# PCBA-2075-02.net
KiCad netlist of a schematic drawn in Altium Designer
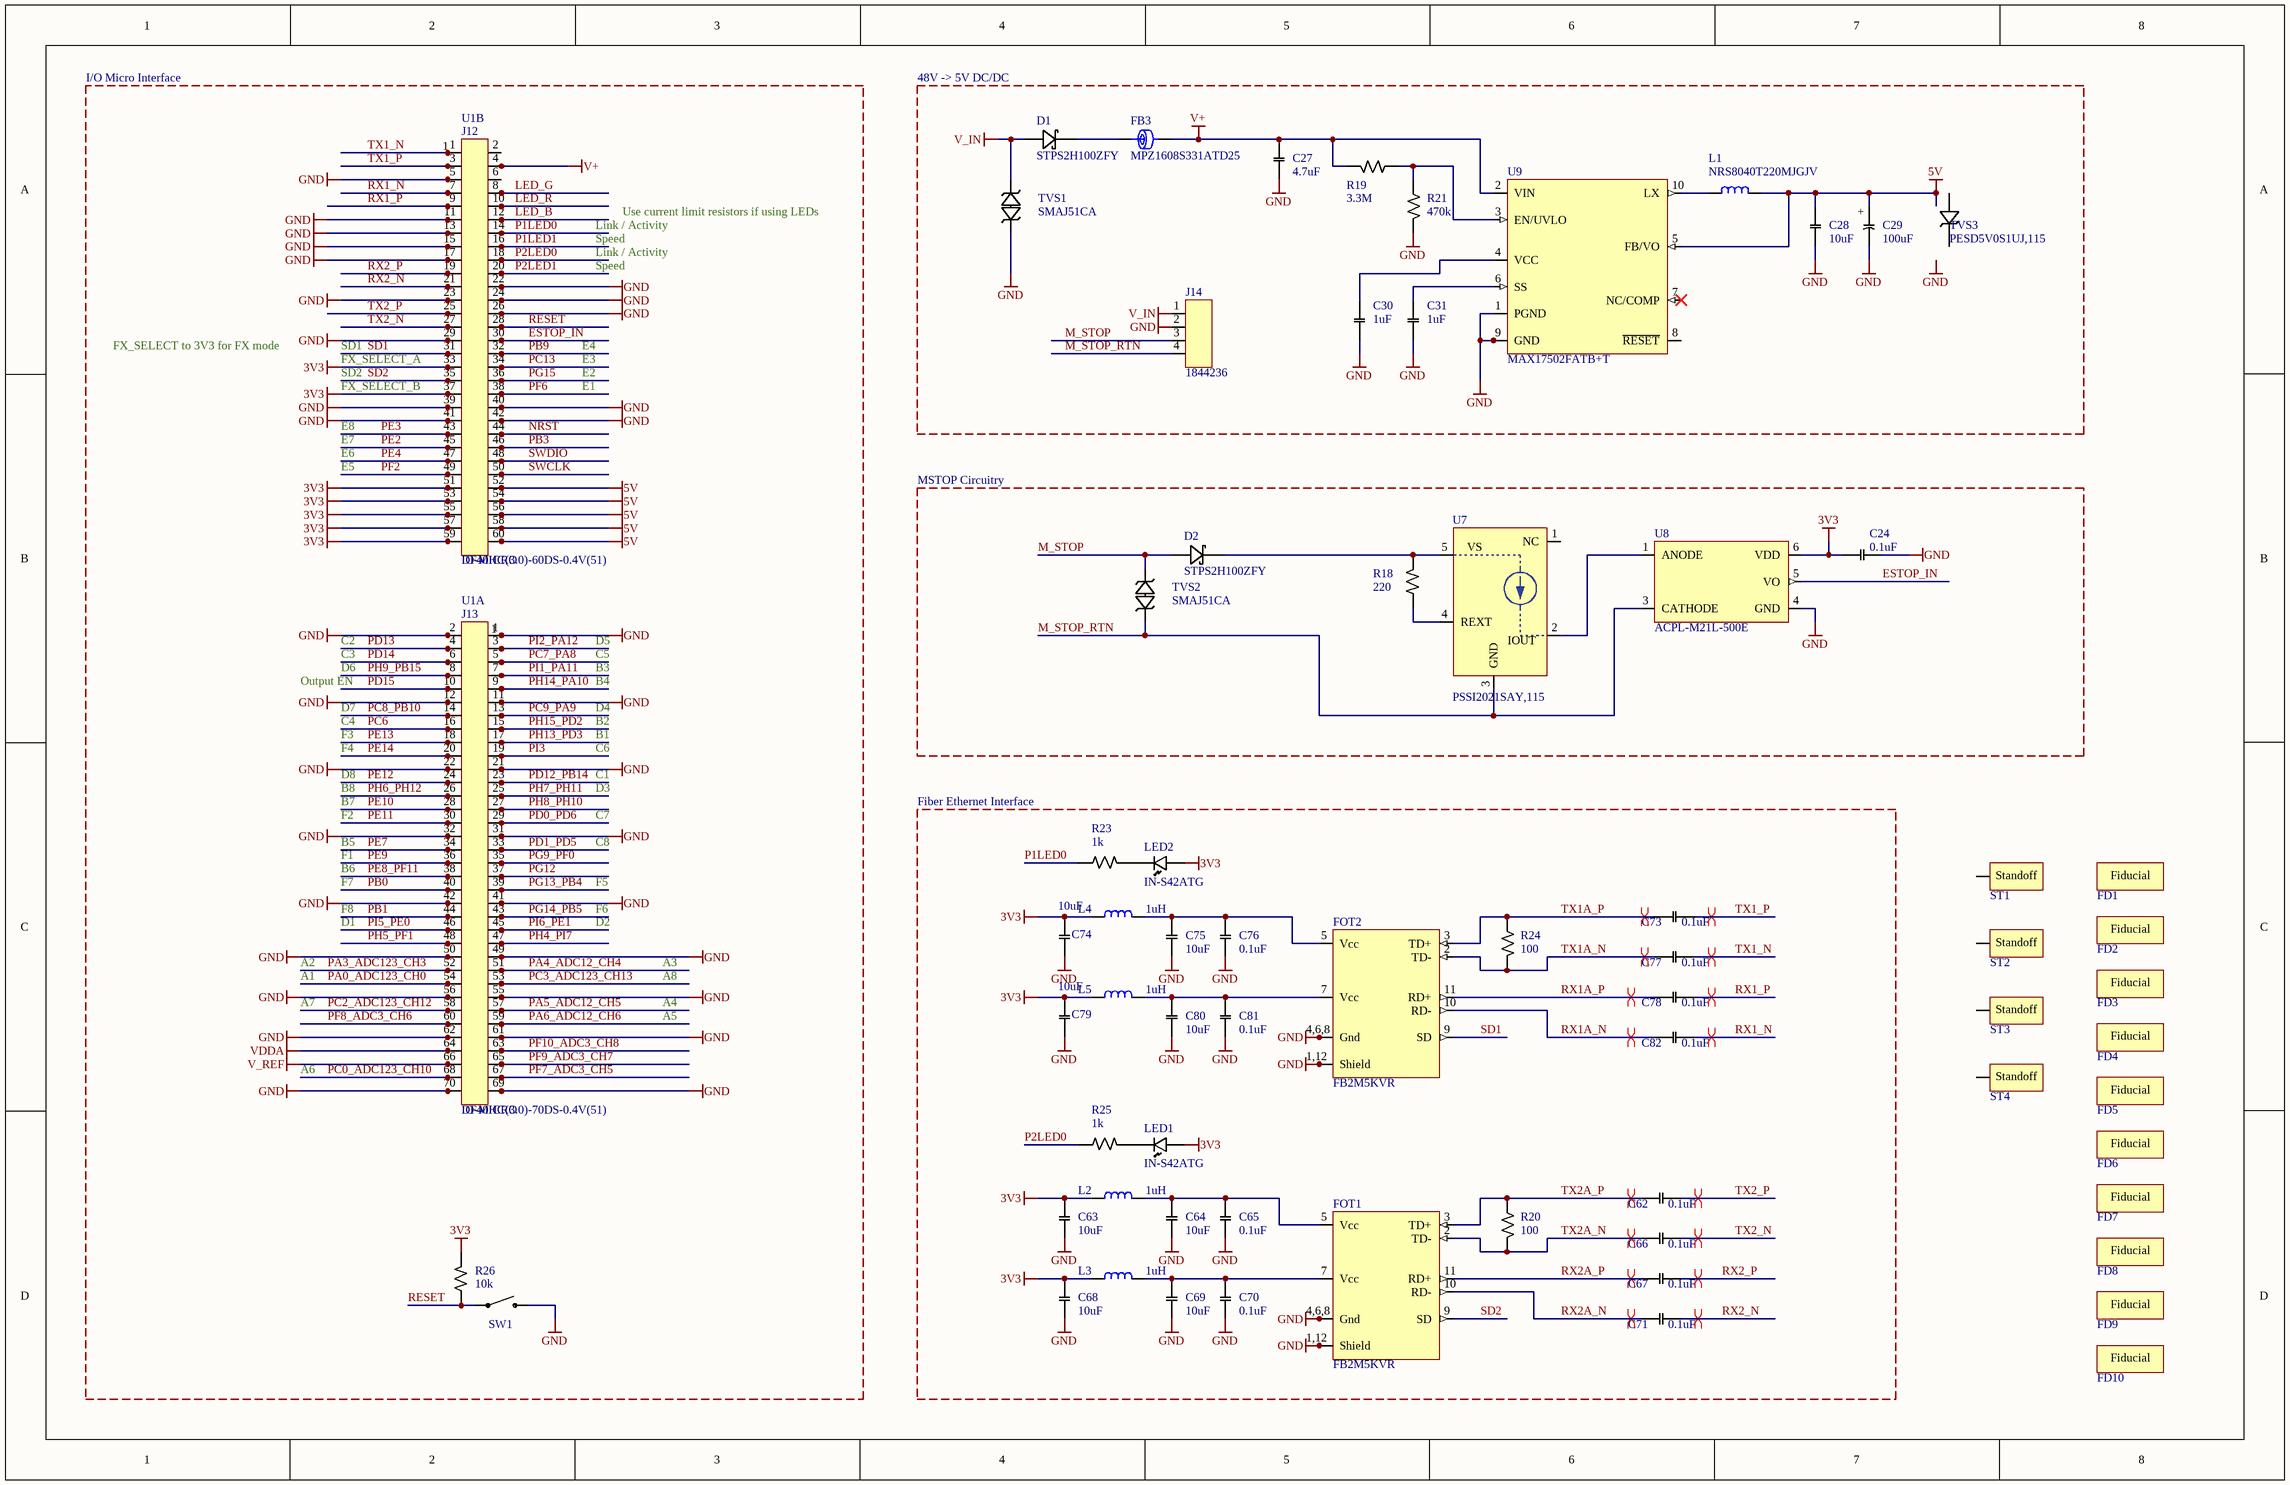
[diagram p0: PCBA-2075-02.SchDoc]

(export (version "E")
  (design (tool "Eeschema 10.0.6"))
  (components
    (comp (ref "C24")
      (value "CMP-00040-11")
      (footprint "C0402")
      (description "Capacitor Ceramic 0.1uF 25V X7R 10% SMD 0402")
      (fields (field (name "TOLERANCE") "10%") (field (name "CAPACITANCE") "0.1uF"))
      (libsource (lib "Hebi Robotics") (part "Capacitor"))
    )
    (comp (ref "C27")
      (value "C-4.7uf-X7S-100V-20%-1210")
      (footprint "C1210")
      (description "Capacitor Ceramic 4.7uF 100V X7S 20% SMD 1210")
      (fields (field (name "TOLERANCE") "±20%") (field (name "CAPACITANCE") "4.7uF"))
      (libsource (lib "Hebi Robotics") (part "Capacitor"))
    )
    (comp (ref "C28")
      (value "C-10uf-X5R-16V-10%-0603")
      (footprint "C0603")
      (description "Capacitor Ceramic 10uF 16V X5R 10% SMD 0603")
      (fields (field (name "TOLERANCE") "10%") (field (name "CAPACITANCE") "10uF"))
      (libsource (lib "Hebi Robotics") (part "Capacitor"))
    )
    (comp (ref "C29")
      (value "16SVPC100M")
      (footprint "CAPAE127P600-8N")
      (description "CAP ALUM POLY 100UF 20% 16V SMD")
      (fields
        (field (name "CAPACITANCE") "100uF")
        (field (name "TOLERANCE") "20%")
        (field (name "VOLTAGE") "16V")
      )
      (libsource (lib "Hebi Robotics") (part "Capacitor_Polarized"))
    )
    (comp (ref "C30")
      (value "C-1uf-X7R-25V-10%-0603")
      (footprint "C0603")
      (description "Capacitor Ceramic 1uF 25V X7R 10% SMD 0603")
      (fields (field (name "TOLERANCE") "10%") (field (name "CAPACITANCE") "1uF"))
      (libsource (lib "Hebi Robotics") (part "Capacitor"))
    )
    (comp (ref "C31")
      (value "C-1uf-X7R-25V-10%-0603")
      (footprint "C0603")
      (description "Capacitor Ceramic 1uF 25V X7R 10% SMD 0603")
      (fields (field (name "TOLERANCE") "10%") (field (name "CAPACITANCE") "1uF"))
      (libsource (lib "Hebi Robotics") (part "Capacitor"))
    )
    (comp (ref "C62")
      (value "CMP-00040-11")
      (footprint "C0402")
      (description "Capacitor Ceramic 0.1uF 25V X7R 10% SMD 0402")
      (fields (field (name "TOLERANCE") "10%") (field (name "CAPACITANCE") "0.1uF"))
      (libsource (lib "Hebi Robotics") (part "Capacitor"))
    )
    (comp (ref "C63")
      (value "C-10uf-X5R-16V-10%-0603")
      (footprint "C0603")
      (description "Capacitor Ceramic 10uF 16V X5R 10% SMD 0603")
      (fields (field (name "TOLERANCE") "10%") (field (name "CAPACITANCE") "10uF"))
      (libsource (lib "Hebi Robotics") (part "Capacitor"))
    )
    (comp (ref "C64")
      (value "C-10uf-X5R-16V-10%-0603")
      (footprint "C0603")
      (description "Capacitor Ceramic 10uF 16V X5R 10% SMD 0603")
      (fields (field (name "TOLERANCE") "10%") (field (name "CAPACITANCE") "10uF"))
      (libsource (lib "Hebi Robotics") (part "Capacitor"))
    )
    (comp (ref "C65")
      (value "CMP-00040-11")
      (footprint "C0402")
      (description "Capacitor Ceramic 0.1uF 25V X7R 10% SMD 0402")
      (fields (field (name "TOLERANCE") "10%") (field (name "CAPACITANCE") "0.1uF"))
      (libsource (lib "Hebi Robotics") (part "Capacitor"))
    )
    (comp (ref "C66")
      (value "CMP-00040-11")
      (footprint "C0402")
      (description "Capacitor Ceramic 0.1uF 25V X7R 10% SMD 0402")
      (fields (field (name "TOLERANCE") "10%") (field (name "CAPACITANCE") "0.1uF"))
      (libsource (lib "Hebi Robotics") (part "Capacitor"))
    )
    (comp (ref "C67")
      (value "CMP-00040-11")
      (footprint "C0402")
      (description "Capacitor Ceramic 0.1uF 25V X7R 10% SMD 0402")
      (fields (field (name "TOLERANCE") "10%") (field (name "CAPACITANCE") "0.1uF"))
      (libsource (lib "Hebi Robotics") (part "Capacitor"))
    )
    (comp (ref "C68")
      (value "C-10uf-X5R-16V-10%-0603")
      (footprint "C0603")
      (description "Capacitor Ceramic 10uF 16V X5R 10% SMD 0603")
      (fields (field (name "TOLERANCE") "10%") (field (name "CAPACITANCE") "10uF"))
      (libsource (lib "Hebi Robotics") (part "Capacitor"))
    )
    (comp (ref "C69")
      (value "C-10uf-X5R-16V-10%-0603")
      (footprint "C0603")
      (description "Capacitor Ceramic 10uF 16V X5R 10% SMD 0603")
      (fields (field (name "TOLERANCE") "10%") (field (name "CAPACITANCE") "10uF"))
      (libsource (lib "Hebi Robotics") (part "Capacitor"))
    )
    (comp (ref "C70")
      (value "CMP-00040-11")
      (footprint "C0402")
      (description "Capacitor Ceramic 0.1uF 25V X7R 10% SMD 0402")
      (fields (field (name "TOLERANCE") "10%") (field (name "CAPACITANCE") "0.1uF"))
      (libsource (lib "Hebi Robotics") (part "Capacitor"))
    )
    (comp (ref "C71")
      (value "CMP-00040-11")
      (footprint "C0402")
      (description "Capacitor Ceramic 0.1uF 25V X7R 10% SMD 0402")
      (fields (field (name "TOLERANCE") "10%") (field (name "CAPACITANCE") "0.1uF"))
      (libsource (lib "Hebi Robotics") (part "Capacitor"))
    )
    (comp (ref "C73")
      (value "CMP-00040-11")
      (footprint "C0402")
      (description "Capacitor Ceramic 0.1uF 25V X7R 10% SMD 0402")
      (fields (field (name "TOLERANCE") "10%") (field (name "CAPACITANCE") "0.1uF"))
      (libsource (lib "Hebi Robotics") (part "Capacitor"))
    )
    (comp (ref "C74")
      (value "C-10uf-X5R-16V-10%-0603")
      (footprint "C0603")
      (description "Capacitor Ceramic 10uF 16V X5R 10% SMD 0603")
      (fields (field (name "TOLERANCE") "10%") (field (name "CAPACITANCE") "10uF"))
      (libsource (lib "Hebi Robotics") (part "Capacitor"))
    )
    (comp (ref "C75")
      (value "C-10uf-X5R-16V-10%-0603")
      (footprint "C0603")
      (description "Capacitor Ceramic 10uF 16V X5R 10% SMD 0603")
      (fields (field (name "TOLERANCE") "10%") (field (name "CAPACITANCE") "10uF"))
      (libsource (lib "Hebi Robotics") (part "Capacitor"))
    )
    (comp (ref "C76")
      (value "CMP-00040-11")
      (footprint "C0402")
      (description "Capacitor Ceramic 0.1uF 25V X7R 10% SMD 0402")
      (fields (field (name "TOLERANCE") "10%") (field (name "CAPACITANCE") "0.1uF"))
      (libsource (lib "Hebi Robotics") (part "Capacitor"))
    )
    (comp (ref "C77")
      (value "CMP-00040-11")
      (footprint "C0402")
      (description "Capacitor Ceramic 0.1uF 25V X7R 10% SMD 0402")
      (fields (field (name "TOLERANCE") "10%") (field (name "CAPACITANCE") "0.1uF"))
      (libsource (lib "Hebi Robotics") (part "Capacitor"))
    )
    (comp (ref "C78")
      (value "CMP-00040-11")
      (footprint "C0402")
      (description "Capacitor Ceramic 0.1uF 25V X7R 10% SMD 0402")
      (fields (field (name "TOLERANCE") "10%") (field (name "CAPACITANCE") "0.1uF"))
      (libsource (lib "Hebi Robotics") (part "Capacitor"))
    )
    (comp (ref "C79")
      (value "C-10uf-X5R-16V-10%-0603")
      (footprint "C0603")
      (description "Capacitor Ceramic 10uF 16V X5R 10% SMD 0603")
      (fields (field (name "TOLERANCE") "10%") (field (name "CAPACITANCE") "10uF"))
      (libsource (lib "Hebi Robotics") (part "Capacitor"))
    )
    (comp (ref "C80")
      (value "C-10uf-X5R-16V-10%-0603")
      (footprint "C0603")
      (description "Capacitor Ceramic 10uF 16V X5R 10% SMD 0603")
      (fields (field (name "TOLERANCE") "10%") (field (name "CAPACITANCE") "10uF"))
      (libsource (lib "Hebi Robotics") (part "Capacitor"))
    )
    (comp (ref "C81")
      (value "CMP-00040-11")
      (footprint "C0402")
      (description "Capacitor Ceramic 0.1uF 25V X7R 10% SMD 0402")
      (fields (field (name "TOLERANCE") "10%") (field (name "CAPACITANCE") "0.1uF"))
      (libsource (lib "Hebi Robotics") (part "Capacitor"))
    )
    (comp (ref "C82")
      (value "CMP-00040-11")
      (footprint "C0402")
      (description "Capacitor Ceramic 0.1uF 25V X7R 10% SMD 0402")
      (fields (field (name "TOLERANCE") "10%") (field (name "CAPACITANCE") "0.1uF"))
      (libsource (lib "Hebi Robotics") (part "Capacitor"))
    )
    (comp (ref "D1")
      (value "STPS2H100ZFY")
      (footprint "SOD123F_ST")
      (description "DIODE SCHOTTKY 100V 2A SOD123F")
      (libsource (lib "Hebi Robotics") (part "SCHOTTKY"))
    )
    (comp (ref "D2")
      (value "STPS2H100ZFY")
      (footprint "SOD123F_ST")
      (description "DIODE SCHOTTKY 100V 2A SOD123F")
      (libsource (lib "Hebi Robotics") (part "SCHOTTKY"))
    )
    (comp (ref "FB3")
      (value "MPZ1608S331ATD25")
      (footprint "FB0603")
      (description "FERRITE CHIP 330 OHM 1.7A 0603")
      (libsource (lib "Hebi Robotics") (part "FB"))
    )
    (comp (ref "FD1")
      (value "FIDUCIAL")
      (footprint "fiducial_01")
      (description "Fiducial")
      (fields (field (name "MANUFACTURER PART NUMBER") "fiducial_01"))
      (libsource (lib "pcb_trace_components") (part "FIDUCIAL"))
    )
    (comp (ref "FD2")
      (value "FIDUCIAL")
      (footprint "fiducial_01")
      (description "Fiducial")
      (fields (field (name "MANUFACTURER PART NUMBER") "fiducial_01"))
      (libsource (lib "pcb_trace_components") (part "FIDUCIAL"))
    )
    (comp (ref "FD3")
      (value "FIDUCIAL")
      (footprint "fiducial_01")
      (description "Fiducial")
      (fields (field (name "MANUFACTURER PART NUMBER") "fiducial_01"))
      (libsource (lib "pcb_trace_components") (part "FIDUCIAL"))
    )
    (comp (ref "FD4")
      (value "FIDUCIAL")
      (footprint "fiducial_01")
      (description "Fiducial")
      (fields (field (name "MANUFACTURER PART NUMBER") "fiducial_01"))
      (libsource (lib "pcb_trace_components") (part "FIDUCIAL"))
    )
    (comp (ref "FD5")
      (value "*")
      (footprint "fiducial_01_no_overlay")
      (description "Fiducial with no overlay")
      (fields (field (name "MANUFACTURER PART NUMBER") "fiducial_01_no_overlay"))
      (libsource (lib "pcb_trace_components") (part "FIDUCIAL"))
    )
    (comp (ref "FD6")
      (value "*")
      (footprint "fiducial_01_no_overlay")
      (description "Fiducial with no overlay")
      (fields (field (name "MANUFACTURER PART NUMBER") "fiducial_01_no_overlay"))
      (libsource (lib "pcb_trace_components") (part "FIDUCIAL"))
    )
    (comp (ref "FD7")
      (value "*")
      (footprint "fiducial_01_no_overlay")
      (description "Fiducial with no overlay")
      (fields (field (name "MANUFACTURER PART NUMBER") "fiducial_01_no_overlay"))
      (libsource (lib "pcb_trace_components") (part "FIDUCIAL"))
    )
    (comp (ref "FD8")
      (value "*")
      (footprint "fiducial_01_no_overlay")
      (description "Fiducial with no overlay")
      (fields (field (name "MANUFACTURER PART NUMBER") "fiducial_01_no_overlay"))
      (libsource (lib "pcb_trace_components") (part "FIDUCIAL"))
    )
    (comp (ref "FD9")
      (value "*")
      (footprint "fiducial_01_no_overlay")
      (description "Fiducial with no overlay")
      (fields (field (name "MANUFACTURER PART NUMBER") "fiducial_01_no_overlay"))
      (libsource (lib "pcb_trace_components") (part "FIDUCIAL"))
    )
    (comp (ref "FD10")
      (value "*")
      (footprint "fiducial_01_no_overlay")
      (description "Fiducial with no overlay")
      (fields (field (name "MANUFACTURER PART NUMBER") "fiducial_01_no_overlay"))
      (libsource (lib "pcb_trace_components") (part "FIDUCIAL"))
    )
    (comp (ref "FOT1")
      (value "FB2M5KVR")
      (footprint "OPTOLOCK")
      (description "Industrial Ethernet Fiber Optic")
      (fields (field (name "MANUFACTURER") "Firecomms"))
      (libsource (lib "Hebi Robotics") (part "OPTOLOCK_D"))
    )
    (comp (ref "FOT2")
      (value "FB2M5KVR")
      (footprint "OPTOLOCK")
      (description "Industrial Ethernet Fiber Optic")
      (fields (field (name "MANUFACTURER") "Firecomms"))
      (libsource (lib "Hebi Robotics") (part "OPTOLOCK_D"))
    )
    (comp (ref "J12")
      (value "DF40HC(3.0)-60DS-0.4V(51)")
      (footprint "DF40HC(3.0)-60DS-0.4V(51)")
      (description "CONN RCPT 60POS 0.4MM SMD GOLD")
      (libsource (lib "Hebi Robotics") (part "CONN_2_ROW_060_POS"))
    )
    (comp (ref "J13")
      (value "DF40HC(3.0)-70DS-0.4V(51)")
      (footprint "DF40HC(3.0)-70DS-0.4V(51)")
      (description "CONN RCPT 70POS 0.4MM SMD GOLD")
      (fields (field (name "MANUFACTURER") "Hirose"))
      (libsource (lib "Hebi Robotics") (part "CONN_2_ROW_070_POS"))
    )
    (comp (ref "J14")
      (value "1844236")
      (footprint "1844236")
      (description "HEADER TERM BLOCK 3.5MM 4POS")
      (fields (field (name "MANUFACTURER") "Phoenix Contact"))
      (libsource (lib "Hebi Robotics") (part "CONN_1_ROW_004_POS"))
    )
    (comp (ref "L1")
      (value "NRS8040T220MJGJV")
      (footprint "NR8040T220M")
      (description "FIXED IND 22UH 2.2A 85.8 MOHM")
      (fields (field (name "TOLERANCE") "±20%"))
      (libsource (lib "Hebi Robotics") (part "Inductor"))
    )
    (comp (ref "L2")
      (value "ASMPH-0603-1R0M-T")
      (footprint "I0603")
      (description "FIXED IND 1UH 1A 200 MOHM SMD")
      (fields (field (name "TOLERANCE") "20%") (field (name "INDUCTANCE") "1uH"))
      (libsource (lib "Hebi Robotics") (part "Inductor"))
    )
    (comp (ref "L3")
      (value "ASMPH-0603-1R0M-T")
      (footprint "I0603")
      (description "FIXED IND 1UH 1A 200 MOHM SMD")
      (fields (field (name "TOLERANCE") "20%") (field (name "INDUCTANCE") "1uH"))
      (libsource (lib "Hebi Robotics") (part "Inductor"))
    )
    (comp (ref "L4")
      (value "ASMPH-0603-1R0M-T")
      (footprint "I0603")
      (description "FIXED IND 1UH 1A 200 MOHM SMD")
      (fields (field (name "TOLERANCE") "20%") (field (name "INDUCTANCE") "1uH"))
      (libsource (lib "Hebi Robotics") (part "Inductor"))
    )
    (comp (ref "L5")
      (value "ASMPH-0603-1R0M-T")
      (footprint "I0603")
      (description "FIXED IND 1UH 1A 200 MOHM SMD")
      (fields (field (name "TOLERANCE") "20%") (field (name "INDUCTANCE") "1uH"))
      (libsource (lib "Hebi Robotics") (part "Inductor"))
    )
    (comp (ref "LED1")
      (value "IN-S42ATG")
      (footprint "IN-S42AT")
      (description "LED GREEN CLEAR 0402 SMD")
      (libsource (lib "Hebi Robotics") (part "LED"))
    )
    (comp (ref "LED2")
      (value "IN-S42ATG")
      (footprint "IN-S42AT")
      (description "LED GREEN CLEAR 0402 SMD")
      (libsource (lib "Hebi Robotics") (part "LED"))
    )
    (comp (ref "R18")
      (value "R-220-1%-0.25w-0603")
      (footprint "R0603")
      (description "Resistor 0603 220 Ohm 1% 1-4 Watt")
      (fields (field (name "POWER") "0.25W, 1/4W") (field (name "RESISTANCE") "220"))
      (libsource (lib "Hebi Robotics") (part "Resistor"))
    )
    (comp (ref "R19")
      (value "R-3.3M-1%-0.063w-0402")
      (footprint "R0402")
      (description "Resistor 0402 3.3M Ohm 1% 1-16 Watt")
      (fields (field (name "POWER") "0.063W, 1/16W") (field (name "RESISTANCE") "3.3M"))
      (libsource (lib "Hebi Robotics") (part "Resistor"))
    )
    (comp (ref "R20")
      (value "100")
      (footprint "R0402")
      (description "Resistor 0402 100 Ohm 1% 1-16 Watt")
      (fields (field (name "POWER") "0.063W, 1/16W") (field (name "TOLERANCE") "1%"))
      (libsource (lib "Hebi Robotics") (part "Resistor"))
    )
    (comp (ref "R21")
      (value "R-470k-1%-0.063w-0402")
      (footprint "R0402")
      (description "Resistor 0402 470k Ohm 1% 1-16 Watt")
      (fields
        (field (name "POWER") "0.063W, 1/16W")
        (field (name "RESISTANCE") "470k")
        (field (name "TOLERANCE") "1%")
      )
      (libsource (lib "Hebi Robotics") (part "Resistor"))
    )
    (comp (ref "R23")
      (value "R-1k-1%-0.063w-0402")
      (footprint "R0402")
      (description "Resistor 0402 1k Ohm 1% 1-16 Watt")
      (fields
        (field (name "POWER") "0.063W, 1/16W")
        (field (name "RESISTANCE") "1k")
        (field (name "TOLERANCE") "1%")
      )
      (libsource (lib "Hebi Robotics") (part "Resistor"))
    )
    (comp (ref "R24")
      (value "100")
      (footprint "R0402")
      (description "Resistor 0402 100 Ohm 1% 1-16 Watt")
      (fields (field (name "POWER") "0.063W, 1/16W") (field (name "TOLERANCE") "1%"))
      (libsource (lib "Hebi Robotics") (part "Resistor"))
    )
    (comp (ref "R25")
      (value "R-1k-1%-0.063w-0402")
      (footprint "R0402")
      (description "Resistor 0402 1k Ohm 1% 1-16 Watt")
      (fields
        (field (name "POWER") "0.063W, 1/16W")
        (field (name "RESISTANCE") "1k")
        (field (name "TOLERANCE") "1%")
      )
      (libsource (lib "Hebi Robotics") (part "Resistor"))
    )
    (comp (ref "R26")
      (value "R-10k-1%-0.063w-0402")
      (footprint "R0402")
      (description "Resistor 0402 10k Ohm 1% 1-16 Watt")
      (fields
        (field (name "POWER") "0.063W, 1/16W")
        (field (name "RESISTANCE") "10k")
        (field (name "TOLERANCE") "1%")
      )
      (libsource (lib "Hebi Robotics") (part "Resistor"))
    )
    (comp (ref "ST1")
      (value "9774030960R")
      (footprint "9774030960R")
      (description "ROUND SPACER M3.3 STEEL 3MM")
      (fields (field (name "MANUFACTURER") "Wurth Electronics Inc"))
      (libsource (lib "Hebi Robotics") (part "STANDOFF_PIN"))
    )
    (comp (ref "ST2")
      (value "9774030960R")
      (footprint "9774030960R")
      (description "ROUND SPACER M3.3 STEEL 3MM")
      (fields (field (name "MANUFACTURER") "Wurth Electronics Inc"))
      (libsource (lib "Hebi Robotics") (part "STANDOFF_PIN"))
    )
    (comp (ref "ST3")
      (value "9774030960R")
      (footprint "9774030960R")
      (description "ROUND SPACER M3.3 STEEL 3MM")
      (fields (field (name "MANUFACTURER") "Wurth Electronics Inc"))
      (libsource (lib "Hebi Robotics") (part "STANDOFF_PIN"))
    )
    (comp (ref "ST4")
      (value "9774030960R")
      (footprint "9774030960R")
      (description "ROUND SPACER M3.3 STEEL 3MM")
      (fields (field (name "MANUFACTURER") "Wurth Electronics Inc"))
      (libsource (lib "Hebi Robotics") (part "STANDOFF_PIN"))
    )
    (comp (ref "SW1")
      (value "222ADVBA")
      (footprint "222ADVBA")
      (description "Tactile Switch SPST-NO Top Actuated Through Hole")
      (fields (field (name "MANUFACTURER") "CTS"))
      (libsource (lib "Hebi Robotics") (part "SPST_NO"))
    )
    (comp (ref "TVS1")
      (value "SMAJ51CA")
      (footprint "SMA_BI_BOURNS")
      (description "TVS DIODE 51VWM 82.4VC DO214AC")
      (libsource (lib "Hebi Robotics") (part "TVS_BI"))
    )
    (comp (ref "TVS2")
      (value "SMAJ51CA")
      (footprint "SMA_BI_BOURNS")
      (description "TVS DIODE 51VWM 82.4VC DO214AC")
      (libsource (lib "Hebi Robotics") (part "TVS_BI"))
    )
    (comp (ref "TVS3")
      (value "PESD5V0S1UJ,115")
      (footprint "SOD-323F_NXP")
      (description "TVS DIODE 5VWM 19VC SOD323F")
      (libsource (lib "Hebi Robotics") (part "TVS"))
    )
    (comp (ref "U1")
      (value "IO-MICRO")
      (footprint "IO-MICRO-Footprint-1")
      (description "IO Micro Composite Component")
      (libsource (lib "Hebi Robotics") (part "IO-MICRO-Symbol-1"))
    )
    (comp (ref "U7")
      (value "PSSI2021SAY,115")
      (footprint "PSSI2021SAY,115")
      (description "Current Source Regulator  50mA 5-TSSOP")
      (libsource (lib "Hebi Robotics") (part "PSSI2021SAY,115"))
    )
    (comp (ref "U8")
      (value "ACPL-M21L-500E")
      (footprint "SOT125P700X260-5N")
      (description "OPTOISO 3.75KV PUSH PULL 5SO")
      (libsource (lib "Hebi Robotics") (part "Symbol"))
    )
    (comp (ref "U9")
      (value "MAX17502FATB+T")
      (footprint "10_TDFN_MAXIM")
      (description "IC REG BUCK 5V 1A SYNC 10TDFN")
      (fields (field (name "MANUFACTURER") "Maxim Integrated"))
      (libsource (lib "Hebi Robotics") (part "MAX17502E_F_G"))
    )
  )
  (nets
    (net (code "1") (name "/ESTOP_IN") (class "Default")
      (node (ref "J12") (pin "30") (pinfunction "30_30") (pintype "passive"))
      (node (ref "U1") (pin "B30") (pinfunction "B30_B30") (pintype "passive"))
      (node (ref "U8") (pin "5") (pinfunction "VO_5") (pintype "output"))
    )
    (net (code "2") (name "/LED_B") (class "Default")
      (node (ref "J12") (pin "12") (pinfunction "12_12") (pintype "passive"))
      (node (ref "U1") (pin "B12") (pinfunction "B12_B12") (pintype "passive"))
    )
    (net (code "3") (name "/LED_G") (class "Default")
      (node (ref "J12") (pin "8") (pinfunction "8_8") (pintype "passive"))
      (node (ref "U1") (pin "B8") (pinfunction "B8_B8") (pintype "passive"))
    )
    (net (code "4") (name "/LED_R") (class "Default")
      (node (ref "J12") (pin "10") (pinfunction "10_10") (pintype "passive"))
      (node (ref "U1") (pin "B10") (pinfunction "B10_B10") (pintype "passive"))
    )
    (net (code "5") (name "/M_STOP") (class "Default")
      (node (ref "D2") (pin "A") (pinfunction "A_A") (pintype "passive"))
      (node (ref "J14") (pin "3") (pinfunction "3_3") (pintype "passive"))
      (node (ref "TVS2") (pin "C") (pinfunction "C_C") (pintype "passive"))
    )
    (net (code "6") (name "/M_STOP_RTN") (class "Default")
      (node (ref "J14") (pin "4") (pinfunction "4_4") (pintype "passive"))
      (node (ref "TVS2") (pin "A") (pinfunction "A_A") (pintype "passive"))
      (node (ref "U7") (pin "3") (pinfunction "GND_3") (pintype "passive"))
      (node (ref "U8") (pin "3") (pinfunction "CATHODE_3") (pintype "passive"))
    )
    (net (code "7") (name "/NRST") (class "Default")
      (node (ref "J12") (pin "44") (pinfunction "44_44") (pintype "passive"))
      (node (ref "U1") (pin "B44") (pinfunction "B44_B44") (pintype "passive"))
    )
    (net (code "8") (name "/P1LED0") (class "Default")
      (node (ref "J12") (pin "14") (pinfunction "14_14") (pintype "passive"))
      (node (ref "R23") (pin "1") (pinfunction "1_1") (pintype "passive"))
      (node (ref "U1") (pin "B14") (pinfunction "B14_B14") (pintype "passive"))
    )
    (net (code "9") (name "/P1LED1") (class "Default")
      (node (ref "J12") (pin "16") (pinfunction "16_16") (pintype "passive"))
      (node (ref "U1") (pin "B16") (pinfunction "B16_B16") (pintype "passive"))
    )
    (net (code "10") (name "/P2LED0") (class "Default")
      (node (ref "J12") (pin "18") (pinfunction "18_18") (pintype "passive"))
      (node (ref "R25") (pin "1") (pinfunction "1_1") (pintype "passive"))
      (node (ref "U1") (pin "B18") (pinfunction "B18_B18") (pintype "passive"))
    )
    (net (code "11") (name "/P2LED1") (class "Default")
      (node (ref "J12") (pin "20") (pinfunction "20_20") (pintype "passive"))
      (node (ref "U1") (pin "B20") (pinfunction "B20_B20") (pintype "passive"))
    )
    (net (code "12") (name "/PA0_ADC123_CH0") (class "Default")
      (node (ref "J13") (pin "54") (pinfunction "54_54") (pintype "passive"))
      (node (ref "U1") (pin "A54") (pinfunction "A54_A54") (pintype "passive"))
    )
    (net (code "13") (name "/PA3_ADC123_CH3") (class "Default")
      (node (ref "J13") (pin "52") (pinfunction "52_52") (pintype "passive"))
      (node (ref "U1") (pin "A52") (pinfunction "A52_A52") (pintype "passive"))
    )
    (net (code "14") (name "/PA4_ADC12_CH4") (class "Default")
      (node (ref "J13") (pin "51") (pinfunction "51_51") (pintype "passive"))
      (node (ref "U1") (pin "A51") (pinfunction "A51_A51") (pintype "passive"))
    )
    (net (code "15") (name "/PA5_ADC12_CH5") (class "Default")
      (node (ref "J13") (pin "57") (pinfunction "57_57") (pintype "passive"))
      (node (ref "U1") (pin "A57") (pinfunction "A57_A57") (pintype "passive"))
    )
    (net (code "16") (name "/PA6_ADC12_CH6") (class "Default")
      (node (ref "J13") (pin "59") (pinfunction "59_59") (pintype "passive"))
      (node (ref "U1") (pin "A59") (pinfunction "A59_A59") (pintype "passive"))
    )
    (net (code "17") (name "/PB0") (class "Default")
      (node (ref "J13") (pin "40") (pinfunction "40_40") (pintype "passive"))
      (node (ref "U1") (pin "A40") (pinfunction "A40_A40") (pintype "passive"))
    )
    (net (code "18") (name "/PB1") (class "Default")
      (node (ref "J13") (pin "44") (pinfunction "44_44") (pintype "passive"))
      (node (ref "U1") (pin "A44") (pinfunction "A44_A44") (pintype "passive"))
    )
    (net (code "19") (name "/PB3") (class "Default")
      (node (ref "J12") (pin "46") (pinfunction "46_46") (pintype "passive"))
      (node (ref "U1") (pin "B46") (pinfunction "B46_B46") (pintype "passive"))
    )
    (net (code "20") (name "/PB9") (class "Default")
      (node (ref "J12") (pin "32") (pinfunction "32_32") (pintype "passive"))
      (node (ref "U1") (pin "B32") (pinfunction "B32_B32") (pintype "passive"))
    )
    (net (code "21") (name "/PC0_ADC123_CH10") (class "Default")
      (node (ref "J13") (pin "68") (pinfunction "68_68") (pintype "passive"))
      (node (ref "U1") (pin "A68") (pinfunction "A68_A68") (pintype "passive"))
    )
    (net (code "22") (name "/PC2_ADC123_CH12") (class "Default")
      (node (ref "J13") (pin "58") (pinfunction "58_58") (pintype "passive"))
      (node (ref "U1") (pin "A58") (pinfunction "A58_A58") (pintype "passive"))
    )
    (net (code "23") (name "/PC3_ADC123_CH13") (class "Default")
      (node (ref "J13") (pin "53") (pinfunction "53_53") (pintype "passive"))
      (node (ref "U1") (pin "A53") (pinfunction "A53_A53") (pintype "passive"))
    )
    (net (code "24") (name "/PC6") (class "Default")
      (node (ref "J13") (pin "16") (pinfunction "16_16") (pintype "passive"))
      (node (ref "U1") (pin "A16") (pinfunction "A16_A16") (pintype "passive"))
    )
    (net (code "25") (name "/PC7_PA8") (class "Default")
      (node (ref "J13") (pin "5") (pinfunction "5_5") (pintype "passive"))
      (node (ref "U1") (pin "A5") (pinfunction "A5_A5") (pintype "passive"))
    )
    (net (code "26") (name "/PC8_PB10") (class "Default")
      (node (ref "J13") (pin "14") (pinfunction "14_14") (pintype "passive"))
      (node (ref "U1") (pin "A14") (pinfunction "A14_A14") (pintype "passive"))
    )
    (net (code "27") (name "/PC9_PA9") (class "Default")
      (node (ref "J13") (pin "13") (pinfunction "13_13") (pintype "passive"))
      (node (ref "U1") (pin "A13") (pinfunction "A13_A13") (pintype "passive"))
    )
    (net (code "28") (name "/PC13") (class "Default")
      (node (ref "J12") (pin "34") (pinfunction "34_34") (pintype "passive"))
      (node (ref "U1") (pin "B34") (pinfunction "B34_B34") (pintype "passive"))
    )
    (net (code "29") (name "/PD0_PD6") (class "Default")
      (node (ref "J13") (pin "29") (pinfunction "29_29") (pintype "passive"))
      (node (ref "U1") (pin "A29") (pinfunction "A29_A29") (pintype "passive"))
    )
    (net (code "30") (name "/PD1_PD5") (class "Default")
      (node (ref "J13") (pin "33") (pinfunction "33_33") (pintype "passive"))
      (node (ref "U1") (pin "A33") (pinfunction "A33_A33") (pintype "passive"))
    )
    (net (code "31") (name "/PD12_PB14") (class "Default")
      (node (ref "J13") (pin "23") (pinfunction "23_23") (pintype "passive"))
      (node (ref "U1") (pin "A23") (pinfunction "A23_A23") (pintype "passive"))
    )
    (net (code "32") (name "/PD13") (class "Default")
      (node (ref "J13") (pin "4") (pinfunction "4_4") (pintype "passive"))
      (node (ref "U1") (pin "A4") (pinfunction "A4_A4") (pintype "passive"))
    )
    (net (code "33") (name "/PD14") (class "Default")
      (node (ref "J13") (pin "6") (pinfunction "6_6") (pintype "passive"))
      (node (ref "U1") (pin "A6") (pinfunction "A6_A6") (pintype "passive"))
    )
    (net (code "34") (name "/PD15") (class "Default")
      (node (ref "J13") (pin "10") (pinfunction "10_10") (pintype "passive"))
      (node (ref "U1") (pin "A10") (pinfunction "A10_A10") (pintype "passive"))
    )
    (net (code "35") (name "/PE2") (class "Default")
      (node (ref "J12") (pin "45") (pinfunction "45_45") (pintype "passive"))
      (node (ref "U1") (pin "B45") (pinfunction "B45_B45") (pintype "passive"))
    )
    (net (code "36") (name "/PE3") (class "Default")
      (node (ref "J12") (pin "43") (pinfunction "43_43") (pintype "passive"))
      (node (ref "U1") (pin "B43") (pinfunction "B43_B43") (pintype "passive"))
    )
    (net (code "37") (name "/PE4") (class "Default")
      (node (ref "J12") (pin "47") (pinfunction "47_47") (pintype "passive"))
      (node (ref "U1") (pin "B47") (pinfunction "B47_B47") (pintype "passive"))
    )
    (net (code "38") (name "/PE7") (class "Default")
      (node (ref "J13") (pin "34") (pinfunction "34_34") (pintype "passive"))
      (node (ref "U1") (pin "A34") (pinfunction "A34_A34") (pintype "passive"))
    )
    (net (code "39") (name "/PE8_PF11") (class "Default")
      (node (ref "J13") (pin "38") (pinfunction "38_38") (pintype "passive"))
      (node (ref "U1") (pin "A38") (pinfunction "A38_A38") (pintype "passive"))
    )
    (net (code "40") (name "/PE9") (class "Default")
      (node (ref "J13") (pin "36") (pinfunction "36_36") (pintype "passive"))
      (node (ref "U1") (pin "A36") (pinfunction "A36_A36") (pintype "passive"))
    )
    (net (code "41") (name "/PE10") (class "Default")
      (node (ref "J13") (pin "28") (pinfunction "28_28") (pintype "passive"))
      (node (ref "U1") (pin "A28") (pinfunction "A28_A28") (pintype "passive"))
    )
    (net (code "42") (name "/PE11") (class "Default")
      (node (ref "J13") (pin "30") (pinfunction "30_30") (pintype "passive"))
      (node (ref "U1") (pin "A30") (pinfunction "A30_A30") (pintype "passive"))
    )
    (net (code "43") (name "/PE12") (class "Default")
      (node (ref "J13") (pin "24") (pinfunction "24_24") (pintype "passive"))
      (node (ref "U1") (pin "A24") (pinfunction "A24_A24") (pintype "passive"))
    )
    (net (code "44") (name "/PE13") (class "Default")
      (node (ref "J13") (pin "18") (pinfunction "18_18") (pintype "passive"))
      (node (ref "U1") (pin "A18") (pinfunction "A18_A18") (pintype "passive"))
    )
    (net (code "45") (name "/PE14") (class "Default")
      (node (ref "J13") (pin "20") (pinfunction "20_20") (pintype "passive"))
      (node (ref "U1") (pin "A20") (pinfunction "A20_A20") (pintype "passive"))
    )
    (net (code "46") (name "/PF2") (class "Default")
      (node (ref "J12") (pin "49") (pinfunction "49_49") (pintype "passive"))
      (node (ref "U1") (pin "B49") (pinfunction "B49_B49") (pintype "passive"))
    )
    (net (code "47") (name "/PF6") (class "Default")
      (node (ref "J12") (pin "38") (pinfunction "38_38") (pintype "passive"))
      (node (ref "U1") (pin "B38") (pinfunction "B38_B38") (pintype "passive"))
    )
    (net (code "48") (name "/PF7_ADC3_CH5") (class "Default")
      (node (ref "J13") (pin "67") (pinfunction "67_67") (pintype "passive"))
      (node (ref "U1") (pin "A67") (pinfunction "A67_A67") (pintype "passive"))
    )
    (net (code "49") (name "/PF8_ADC3_CH6") (class "Default")
      (node (ref "J13") (pin "60") (pinfunction "60_60") (pintype "passive"))
      (node (ref "U1") (pin "A60") (pinfunction "A60_A60") (pintype "passive"))
    )
    (net (code "50") (name "/PF9_ADC3_CH7") (class "Default")
      (node (ref "J13") (pin "65") (pinfunction "65_65") (pintype "passive"))
      (node (ref "U1") (pin "A65") (pinfunction "A65_A65") (pintype "passive"))
    )
    (net (code "51") (name "/PF10_ADC3_CH8") (class "Default")
      (node (ref "J13") (pin "63") (pinfunction "63_63") (pintype "passive"))
      (node (ref "U1") (pin "A63") (pinfunction "A63_A63") (pintype "passive"))
    )
    (net (code "52") (name "/PG9_PF0") (class "Default")
      (node (ref "J13") (pin "35") (pinfunction "35_35") (pintype "passive"))
      (node (ref "U1") (pin "A35") (pinfunction "A35_A35") (pintype "passive"))
    )
    (net (code "53") (name "/PG12") (class "Default")
      (node (ref "J13") (pin "37") (pinfunction "37_37") (pintype "passive"))
      (node (ref "U1") (pin "A37") (pinfunction "A37_A37") (pintype "passive"))
    )
    (net (code "54") (name "/PG13_PB4") (class "Default")
      (node (ref "J13") (pin "39") (pinfunction "39_39") (pintype "passive"))
      (node (ref "U1") (pin "A39") (pinfunction "A39_A39") (pintype "passive"))
    )
    (net (code "55") (name "/PG14_PB5") (class "Default")
      (node (ref "J13") (pin "43") (pinfunction "43_43") (pintype "passive"))
      (node (ref "U1") (pin "A43") (pinfunction "A43_A43") (pintype "passive"))
    )
    (net (code "56") (name "/PG15") (class "Default")
      (node (ref "J12") (pin "36") (pinfunction "36_36") (pintype "passive"))
      (node (ref "U1") (pin "B36") (pinfunction "B36_B36") (pintype "passive"))
    )
    (net (code "57") (name "/PH4_PI7") (class "Default")
      (node (ref "J13") (pin "47") (pinfunction "47_47") (pintype "passive"))
      (node (ref "U1") (pin "A47") (pinfunction "A47_A47") (pintype "passive"))
    )
    (net (code "58") (name "/PH5_PF1") (class "Default")
      (node (ref "J13") (pin "48") (pinfunction "48_48") (pintype "passive"))
      (node (ref "U1") (pin "A48") (pinfunction "A48_A48") (pintype "passive"))
    )
    (net (code "59") (name "/PH6_PH12") (class "Default")
      (node (ref "J13") (pin "26") (pinfunction "26_26") (pintype "passive"))
      (node (ref "U1") (pin "A26") (pinfunction "A26_A26") (pintype "passive"))
    )
    (net (code "60") (name "/PH7_PH11") (class "Default")
      (node (ref "J13") (pin "25") (pinfunction "25_25") (pintype "passive"))
      (node (ref "U1") (pin "A25") (pinfunction "A25_A25") (pintype "passive"))
    )
    (net (code "61") (name "/PH8_PH10") (class "Default")
      (node (ref "J13") (pin "27") (pinfunction "27_27") (pintype "passive"))
      (node (ref "U1") (pin "A27") (pinfunction "A27_A27") (pintype "passive"))
    )
    (net (code "62") (name "/PH9_PB15") (class "Default")
      (node (ref "J13") (pin "8") (pinfunction "8_8") (pintype "passive"))
      (node (ref "U1") (pin "A8") (pinfunction "A8_A8") (pintype "passive"))
    )
    (net (code "63") (name "/PH13_PD3") (class "Default")
      (node (ref "J13") (pin "17") (pinfunction "17_17") (pintype "passive"))
      (node (ref "U1") (pin "A17") (pinfunction "A17_A17") (pintype "passive"))
    )
    (net (code "64") (name "/PH14_PA10") (class "Default")
      (node (ref "J13") (pin "9") (pinfunction "9_9") (pintype "passive"))
      (node (ref "U1") (pin "A9") (pinfunction "A9_A9") (pintype "passive"))
    )
    (net (code "65") (name "/PH15_PD2") (class "Default")
      (node (ref "J13") (pin "15") (pinfunction "15_15") (pintype "passive"))
      (node (ref "U1") (pin "A15") (pinfunction "A15_A15") (pintype "passive"))
    )
    (net (code "66") (name "/PI1_PA11") (class "Default")
      (node (ref "J13") (pin "7") (pinfunction "7_7") (pintype "passive"))
      (node (ref "U1") (pin "A7") (pinfunction "A7_A7") (pintype "passive"))
    )
    (net (code "67") (name "/PI2_PA12") (class "Default")
      (node (ref "J13") (pin "3") (pinfunction "3_3") (pintype "passive"))
      (node (ref "U1") (pin "A3") (pinfunction "A3_A3") (pintype "passive"))
    )
    (net (code "68") (name "/PI3") (class "Default")
      (node (ref "J13") (pin "19") (pinfunction "19_19") (pintype "passive"))
      (node (ref "U1") (pin "A19") (pinfunction "A19_A19") (pintype "passive"))
    )
    (net (code "69") (name "/PI5_PE0") (class "Default")
      (node (ref "J13") (pin "46") (pinfunction "46_46") (pintype "passive"))
      (node (ref "U1") (pin "A46") (pinfunction "A46_A46") (pintype "passive"))
    )
    (net (code "70") (name "/PI6_PE1") (class "Default")
      (node (ref "J13") (pin "45") (pinfunction "45_45") (pintype "passive"))
      (node (ref "U1") (pin "A45") (pinfunction "A45_A45") (pintype "passive"))
    )
    (net (code "71") (name "/RESET") (class "Default")
      (node (ref "J12") (pin "28") (pinfunction "28_28") (pintype "passive"))
      (node (ref "R26") (pin "1") (pinfunction "1_1") (pintype "passive"))
      (node (ref "SW1") (pin "1") (pinfunction "1_1") (pintype "passive"))
      (node (ref "U1") (pin "B28") (pinfunction "B28_B28") (pintype "passive"))
    )
    (net (code "72") (name "/RX1A_N") (class "Default")
      (node (ref "C82") (pin "1") (pinfunction "1_1") (pintype "passive"))
      (node (ref "FOT2") (pin "10") (pinfunction "RD-_10") (pintype "output"))
    )
    (net (code "73") (name "/RX1A_P") (class "Default")
      (node (ref "C78") (pin "1") (pinfunction "1_1") (pintype "passive"))
      (node (ref "FOT2") (pin "11") (pinfunction "RD+_11") (pintype "output"))
    )
    (net (code "74") (name "/RX1_N") (class "Default")
      (node (ref "C82") (pin "2") (pinfunction "2_2") (pintype "passive"))
      (node (ref "J12") (pin "7") (pinfunction "7_7") (pintype "passive"))
      (node (ref "U1") (pin "B7") (pinfunction "B7_B7") (pintype "passive"))
    )
    (net (code "75") (name "/RX1_P") (class "Default")
      (node (ref "C78") (pin "2") (pinfunction "2_2") (pintype "passive"))
      (node (ref "J12") (pin "9") (pinfunction "9_9") (pintype "passive"))
      (node (ref "U1") (pin "B9") (pinfunction "B9_B9") (pintype "passive"))
    )
    (net (code "76") (name "/RX2A_N") (class "Default")
      (node (ref "C71") (pin "2") (pinfunction "2_2") (pintype "passive"))
      (node (ref "FOT1") (pin "10") (pinfunction "RD-_10") (pintype "output"))
    )
    (net (code "77") (name "/RX2A_P") (class "Default")
      (node (ref "C67") (pin "2") (pinfunction "2_2") (pintype "passive"))
      (node (ref "FOT1") (pin "11") (pinfunction "RD+_11") (pintype "output"))
    )
    (net (code "78") (name "/RX2_N") (class "Default")
      (node (ref "C71") (pin "1") (pinfunction "1_1") (pintype "passive"))
      (node (ref "J12") (pin "21") (pinfunction "21_21") (pintype "passive"))
      (node (ref "U1") (pin "B21") (pinfunction "B21_B21") (pintype "passive"))
    )
    (net (code "79") (name "/RX2_P") (class "Default")
      (node (ref "C67") (pin "1") (pinfunction "1_1") (pintype "passive"))
      (node (ref "J12") (pin "19") (pinfunction "19_19") (pintype "passive"))
      (node (ref "U1") (pin "B19") (pinfunction "B19_B19") (pintype "passive"))
    )
    (net (code "80") (name "/SD1") (class "Default")
      (node (ref "FOT2") (pin "9") (pinfunction "SD_9") (pintype "output"))
      (node (ref "J12") (pin "31") (pinfunction "31_31") (pintype "passive"))
      (node (ref "U1") (pin "B31") (pinfunction "B31_B31") (pintype "passive"))
    )
    (net (code "81") (name "/SD2") (class "Default")
      (node (ref "FOT1") (pin "9") (pinfunction "SD_9") (pintype "output"))
      (node (ref "J12") (pin "35") (pinfunction "35_35") (pintype "passive"))
      (node (ref "U1") (pin "B35") (pinfunction "B35_B35") (pintype "passive"))
    )
    (net (code "82") (name "/SWCLK") (class "Default")
      (node (ref "J12") (pin "50") (pinfunction "50_50") (pintype "passive"))
      (node (ref "U1") (pin "B50") (pinfunction "B50_B50") (pintype "passive"))
    )
    (net (code "83") (name "/SWDIO") (class "Default")
      (node (ref "J12") (pin "48") (pinfunction "48_48") (pintype "passive"))
      (node (ref "U1") (pin "B48") (pinfunction "B48_B48") (pintype "passive"))
    )
    (net (code "84") (name "/TX1A_N") (class "Default")
      (node (ref "C77") (pin "1") (pinfunction "1_1") (pintype "passive"))
      (node (ref "FOT2") (pin "2") (pinfunction "TD-_2") (pintype "input"))
      (node (ref "R24") (pin "2") (pinfunction "2_2") (pintype "passive"))
    )
    (net (code "85") (name "/TX1A_P") (class "Default")
      (node (ref "C73") (pin "1") (pinfunction "1_1") (pintype "passive"))
      (node (ref "FOT2") (pin "3") (pinfunction "TD+_3") (pintype "input"))
      (node (ref "R24") (pin "1") (pinfunction "1_1") (pintype "passive"))
    )
    (net (code "86") (name "/TX1_N") (class "Default")
      (node (ref "C77") (pin "2") (pinfunction "2_2") (pintype "passive"))
      (node (ref "J12") (pin "1") (pinfunction "1_1") (pintype "passive"))
      (node (ref "U1") (pin "B1") (pinfunction "B1_B1") (pintype "passive"))
    )
    (net (code "87") (name "/TX1_P") (class "Default")
      (node (ref "C73") (pin "2") (pinfunction "2_2") (pintype "passive"))
      (node (ref "J12") (pin "3") (pinfunction "3_3") (pintype "passive"))
      (node (ref "U1") (pin "B3") (pinfunction "B3_B3") (pintype "passive"))
    )
    (net (code "88") (name "/TX2A_N") (class "Default")
      (node (ref "C66") (pin "2") (pinfunction "2_2") (pintype "passive"))
      (node (ref "FOT1") (pin "2") (pinfunction "TD-_2") (pintype "input"))
      (node (ref "R20") (pin "2") (pinfunction "2_2") (pintype "passive"))
    )
    (net (code "89") (name "/TX2A_P") (class "Default")
      (node (ref "C62") (pin "2") (pinfunction "2_2") (pintype "passive"))
      (node (ref "FOT1") (pin "3") (pinfunction "TD+_3") (pintype "input"))
      (node (ref "R20") (pin "1") (pinfunction "1_1") (pintype "passive"))
    )
    (net (code "90") (name "/TX2_N") (class "Default")
      (node (ref "C66") (pin "1") (pinfunction "1_1") (pintype "passive"))
      (node (ref "J12") (pin "27") (pinfunction "27_27") (pintype "passive"))
      (node (ref "U1") (pin "B27") (pinfunction "B27_B27") (pintype "passive"))
    )
    (net (code "91") (name "/TX2_P") (class "Default")
      (node (ref "C62") (pin "1") (pinfunction "1_1") (pintype "passive"))
      (node (ref "J12") (pin "25") (pinfunction "25_25") (pintype "passive"))
      (node (ref "U1") (pin "B25") (pinfunction "B25_B25") (pintype "passive"))
    )
    (net (code "92") (name "3V3") (class "Default")
      (node (ref "C24") (pin "1") (pinfunction "1_1") (pintype "passive"))
      (node (ref "C63") (pin "2") (pinfunction "2_2") (pintype "passive"))
      (node (ref "C68") (pin "2") (pinfunction "2_2") (pintype "passive"))
      (node (ref "C74") (pin "2") (pinfunction "2_2") (pintype "passive"))
      (node (ref "C79") (pin "2") (pinfunction "2_2") (pintype "passive"))
      (node (ref "J12") (pin "33") (pinfunction "33_33") (pintype "passive"))
      (node (ref "J12") (pin "37") (pinfunction "37_37") (pintype "passive"))
      (node (ref "J12") (pin "51") (pinfunction "51_51") (pintype "passive"))
      (node (ref "J12") (pin "53") (pinfunction "53_53") (pintype "passive"))
      (node (ref "J12") (pin "55") (pinfunction "55_55") (pintype "passive"))
      (node (ref "J12") (pin "57") (pinfunction "57_57") (pintype "passive"))
      (node (ref "J12") (pin "59") (pinfunction "59_59") (pintype "passive"))
      (node (ref "L2") (pin "1") (pinfunction "1_1") (pintype "passive"))
      (node (ref "L3") (pin "1") (pinfunction "1_1") (pintype "passive"))
      (node (ref "L4") (pin "1") (pinfunction "1_1") (pintype "passive"))
      (node (ref "L5") (pin "1") (pinfunction "1_1") (pintype "passive"))
      (node (ref "LED1") (pin "A") (pinfunction "A_A") (pintype "passive"))
      (node (ref "LED2") (pin "A") (pinfunction "A_A") (pintype "passive"))
      (node (ref "R26") (pin "2") (pinfunction "2_2") (pintype "passive"))
      (node (ref "U1") (pin "B33") (pinfunction "B33_B33") (pintype "passive"))
      (node (ref "U1") (pin "B37") (pinfunction "B37_B37") (pintype "passive"))
      (node (ref "U1") (pin "B51") (pinfunction "B51_B51") (pintype "passive"))
      (node (ref "U1") (pin "B53") (pinfunction "B53_B53") (pintype "passive"))
      (node (ref "U1") (pin "B55") (pinfunction "B55_B55") (pintype "passive"))
      (node (ref "U1") (pin "B57") (pinfunction "B57_B57") (pintype "passive"))
      (node (ref "U1") (pin "B59") (pinfunction "B59_B59") (pintype "passive"))
      (node (ref "U8") (pin "6") (pinfunction "VDD_6") (pintype "power_in"))
    )
    (net (code "93") (name "5V") (class "Default")
      (node (ref "C28") (pin "2") (pinfunction "2_2") (pintype "passive"))
      (node (ref "C29") (pin "+") (pinfunction "+_+") (pintype "passive"))
      (node (ref "J12") (pin "52") (pinfunction "52_52") (pintype "passive"))
      (node (ref "J12") (pin "54") (pinfunction "54_54") (pintype "passive"))
      (node (ref "J12") (pin "56") (pinfunction "56_56") (pintype "passive"))
      (node (ref "J12") (pin "58") (pinfunction "58_58") (pintype "passive"))
      (node (ref "J12") (pin "60") (pinfunction "60_60") (pintype "passive"))
      (node (ref "L1") (pin "2") (pinfunction "2_2") (pintype "passive"))
      (node (ref "U1") (pin "B52") (pinfunction "B52_B52") (pintype "passive"))
      (node (ref "U1") (pin "B54") (pinfunction "B54_B54") (pintype "passive"))
      (node (ref "U1") (pin "B56") (pinfunction "B56_B56") (pintype "passive"))
      (node (ref "U1") (pin "B58") (pinfunction "B58_B58") (pintype "passive"))
      (node (ref "U1") (pin "B60") (pinfunction "B60_B60") (pintype "passive"))
      (node (ref "U9") (pin "5") (pinfunction "FB/VO_5") (pintype "input"))
    )
    (net (code "94") (name "GND") (class "Default")
      (node (ref "C24") (pin "2") (pinfunction "2_2") (pintype "passive"))
      (node (ref "C27") (pin "1") (pinfunction "1_1") (pintype "passive"))
      (node (ref "C28") (pin "1") (pinfunction "1_1") (pintype "passive"))
      (node (ref "C29") (pin "-") (pinfunction "-_-") (pintype "passive"))
      (node (ref "C30") (pin "2") (pinfunction "2_2") (pintype "passive"))
      (node (ref "C31") (pin "2") (pinfunction "2_2") (pintype "passive"))
      (node (ref "C63") (pin "1") (pinfunction "1_1") (pintype "passive"))
      (node (ref "C64") (pin "1") (pinfunction "1_1") (pintype "passive"))
      (node (ref "C65") (pin "1") (pinfunction "1_1") (pintype "passive"))
      (node (ref "C68") (pin "1") (pinfunction "1_1") (pintype "passive"))
      (node (ref "C69") (pin "1") (pinfunction "1_1") (pintype "passive"))
      (node (ref "C70") (pin "2") (pinfunction "2_2") (pintype "passive"))
      (node (ref "C74") (pin "1") (pinfunction "1_1") (pintype "passive"))
      (node (ref "C75") (pin "1") (pinfunction "1_1") (pintype "passive"))
      (node (ref "C76") (pin "1") (pinfunction "1_1") (pintype "passive"))
      (node (ref "C79") (pin "1") (pinfunction "1_1") (pintype "passive"))
      (node (ref "C80") (pin "1") (pinfunction "1_1") (pintype "passive"))
      (node (ref "C81") (pin "2") (pinfunction "2_2") (pintype "passive"))
      (node (ref "FOT1") (pin "1") (pinfunction "Shield_1") (pintype "passive"))
      (node (ref "FOT1") (pin "12") (pinfunction "Shield_12") (pintype "passive"))
      (node (ref "FOT1") (pin "4") (pinfunction "Gnd_4") (pintype "power_in"))
      (node (ref "FOT1") (pin "6") (pinfunction "Gnd_6") (pintype "power_in"))
      (node (ref "FOT1") (pin "8") (pinfunction "Gnd_8") (pintype "power_in"))
      (node (ref "FOT2") (pin "1") (pinfunction "Shield_1") (pintype "passive"))
      (node (ref "FOT2") (pin "12") (pinfunction "Shield_12") (pintype "passive"))
      (node (ref "FOT2") (pin "4") (pinfunction "Gnd_4") (pintype "power_in"))
      (node (ref "FOT2") (pin "6") (pinfunction "Gnd_6") (pintype "power_in"))
      (node (ref "FOT2") (pin "8") (pinfunction "Gnd_8") (pintype "power_in"))
      (node (ref "J12") (pin "11") (pinfunction "11_11") (pintype "passive"))
      (node (ref "J12") (pin "13") (pinfunction "13_13") (pintype "passive"))
      (node (ref "J12") (pin "15") (pinfunction "15_15") (pintype "passive"))
      (node (ref "J12") (pin "17") (pinfunction "17_17") (pintype "passive"))
      (node (ref "J12") (pin "22") (pinfunction "22_22") (pintype "passive"))
      (node (ref "J12") (pin "23") (pinfunction "23_23") (pintype "passive"))
      (node (ref "J12") (pin "24") (pinfunction "24_24") (pintype "passive"))
      (node (ref "J12") (pin "26") (pinfunction "26_26") (pintype "passive"))
      (node (ref "J12") (pin "29") (pinfunction "29_29") (pintype "passive"))
      (node (ref "J12") (pin "39") (pinfunction "39_39") (pintype "passive"))
      (node (ref "J12") (pin "40") (pinfunction "40_40") (pintype "passive"))
      (node (ref "J12") (pin "41") (pinfunction "41_41") (pintype "passive"))
      (node (ref "J12") (pin "42") (pinfunction "42_42") (pintype "passive"))
      (node (ref "J12") (pin "5") (pinfunction "5_5") (pintype "passive"))
      (node (ref "J13") (pin "1") (pinfunction "1_1") (pintype "passive"))
      (node (ref "J13") (pin "11") (pinfunction "11_11") (pintype "passive"))
      (node (ref "J13") (pin "12") (pinfunction "12_12") (pintype "passive"))
      (node (ref "J13") (pin "2") (pinfunction "2_2") (pintype "passive"))
      (node (ref "J13") (pin "21") (pinfunction "21_21") (pintype "passive"))
      (node (ref "J13") (pin "22") (pinfunction "22_22") (pintype "passive"))
      (node (ref "J13") (pin "31") (pinfunction "31_31") (pintype "passive"))
      (node (ref "J13") (pin "32") (pinfunction "32_32") (pintype "passive"))
      (node (ref "J13") (pin "41") (pinfunction "41_41") (pintype "passive"))
      (node (ref "J13") (pin "42") (pinfunction "42_42") (pintype "passive"))
      (node (ref "J13") (pin "49") (pinfunction "49_49") (pintype "passive"))
      (node (ref "J13") (pin "50") (pinfunction "50_50") (pintype "passive"))
      (node (ref "J13") (pin "55") (pinfunction "55_55") (pintype "passive"))
      (node (ref "J13") (pin "56") (pinfunction "56_56") (pintype "passive"))
      (node (ref "J13") (pin "61") (pinfunction "61_61") (pintype "passive"))
      (node (ref "J13") (pin "62") (pinfunction "62_62") (pintype "passive"))
      (node (ref "J13") (pin "69") (pinfunction "69_69") (pintype "passive"))
      (node (ref "J13") (pin "70") (pinfunction "70_70") (pintype "passive"))
      (node (ref "J14") (pin "2") (pinfunction "2_2") (pintype "passive"))
      (node (ref "R21") (pin "2") (pinfunction "2_2") (pintype "passive"))
      (node (ref "SW1") (pin "2") (pinfunction "2_2") (pintype "passive"))
      (node (ref "TVS1") (pin "A") (pinfunction "A_A") (pintype "passive"))
      (node (ref "U1") (pin "A1") (pinfunction "A1_A1") (pintype "passive"))
      (node (ref "U1") (pin "A11") (pinfunction "A11_A11") (pintype "passive"))
      (node (ref "U1") (pin "A12") (pinfunction "A12_A12") (pintype "passive"))
      (node (ref "U1") (pin "A2") (pinfunction "A2_A2") (pintype "passive"))
      (node (ref "U1") (pin "A21") (pinfunction "A21_A21") (pintype "passive"))
      (node (ref "U1") (pin "A22") (pinfunction "A22_A22") (pintype "passive"))
      (node (ref "U1") (pin "A31") (pinfunction "A31_A31") (pintype "passive"))
      (node (ref "U1") (pin "A32") (pinfunction "A32_A32") (pintype "passive"))
      (node (ref "U1") (pin "A41") (pinfunction "A41_A41") (pintype "passive"))
      (node (ref "U1") (pin "A42") (pinfunction "A42_A42") (pintype "passive"))
      (node (ref "U1") (pin "A49") (pinfunction "A49_A49") (pintype "passive"))
      (node (ref "U1") (pin "A50") (pinfunction "A50_A50") (pintype "passive"))
      (node (ref "U1") (pin "A55") (pinfunction "A55_A55") (pintype "passive"))
      (node (ref "U1") (pin "A56") (pinfunction "A56_A56") (pintype "passive"))
      (node (ref "U1") (pin "A61") (pinfunction "A61_A61") (pintype "passive"))
      (node (ref "U1") (pin "A62") (pinfunction "A62_A62") (pintype "passive"))
      (node (ref "U1") (pin "A69") (pinfunction "A69_A69") (pintype "passive"))
      (node (ref "U1") (pin "A70") (pinfunction "A70_A70") (pintype "passive"))
      (node (ref "U1") (pin "B11") (pinfunction "B11_B11") (pintype "passive"))
      (node (ref "U1") (pin "B13") (pinfunction "B13_B13") (pintype "passive"))
      (node (ref "U1") (pin "B15") (pinfunction "B15_B15") (pintype "passive"))
      (node (ref "U1") (pin "B17") (pinfunction "B17_B17") (pintype "passive"))
      (node (ref "U1") (pin "B22") (pinfunction "B22_B22") (pintype "passive"))
      (node (ref "U1") (pin "B23") (pinfunction "B23_B23") (pintype "passive"))
      (node (ref "U1") (pin "B24") (pinfunction "B24_B24") (pintype "passive"))
      (node (ref "U1") (pin "B26") (pinfunction "B26_B26") (pintype "passive"))
      (node (ref "U1") (pin "B29") (pinfunction "B29_B29") (pintype "passive"))
      (node (ref "U1") (pin "B39") (pinfunction "B39_B39") (pintype "passive"))
      (node (ref "U1") (pin "B40") (pinfunction "B40_B40") (pintype "passive"))
      (node (ref "U1") (pin "B41") (pinfunction "B41_B41") (pintype "passive"))
      (node (ref "U1") (pin "B42") (pinfunction "B42_B42") (pintype "passive"))
      (node (ref "U1") (pin "B5") (pinfunction "B5_B5") (pintype "passive"))
      (node (ref "U8") (pin "4") (pinfunction "GND_4") (pintype "power_in"))
      (node (ref "U9") (pin "1") (pinfunction "PGND_1") (pintype "power_in"))
      (node (ref "U9") (pin "11") (pinfunction "GND_11") (pintype "power_in"))
      (node (ref "U9") (pin "9") (pinfunction "GND_9") (pintype "power_in"))
    )
    (net (code "95") (name "Net-(C64-Pad2)") (class "Default")
      (node (ref "C64") (pin "2") (pinfunction "2_2") (pintype "passive"))
      (node (ref "C65") (pin "2") (pinfunction "2_2") (pintype "passive"))
      (node (ref "FOT1") (pin "5") (pinfunction "Vcc_5") (pintype "power_in"))
      (node (ref "L2") (pin "2") (pinfunction "2_2") (pintype "passive"))
    )
    (net (code "96") (name "Net-(C69-Pad2)") (class "Default")
      (node (ref "C69") (pin "2") (pinfunction "2_2") (pintype "passive"))
      (node (ref "C70") (pin "1") (pinfunction "1_1") (pintype "passive"))
      (node (ref "FOT1") (pin "7") (pinfunction "Vcc_7") (pintype "power_in"))
      (node (ref "L3") (pin "2") (pinfunction "2_2") (pintype "passive"))
    )
    (net (code "97") (name "Net-(C75-Pad2)") (class "Default")
      (node (ref "C75") (pin "2") (pinfunction "2_2") (pintype "passive"))
      (node (ref "C76") (pin "2") (pinfunction "2_2") (pintype "passive"))
      (node (ref "FOT2") (pin "5") (pinfunction "Vcc_5") (pintype "power_in"))
      (node (ref "L4") (pin "2") (pinfunction "2_2") (pintype "passive"))
    )
    (net (code "98") (name "Net-(C80-Pad2)") (class "Default")
      (node (ref "C80") (pin "2") (pinfunction "2_2") (pintype "passive"))
      (node (ref "C81") (pin "1") (pinfunction "1_1") (pintype "passive"))
      (node (ref "FOT2") (pin "7") (pinfunction "Vcc_7") (pintype "power_in"))
      (node (ref "L5") (pin "2") (pinfunction "2_2") (pintype "passive"))
    )
    (net (code "99") (name "Net-(D1-PadC)") (class "Default")
      (node (ref "D1") (pin "C") (pinfunction "C_C") (pintype "passive"))
      (node (ref "FB3") (pin "1") (pinfunction "1_1") (pintype "passive"))
    )
    (net (code "100") (name "Net-(J12-Pad2)") (class "Default")
      (node (ref "J12") (pin "2") (pinfunction "2_2") (pintype "passive"))
      (node (ref "U1") (pin "B2") (pinfunction "B2_B2") (pintype "passive"))
    )
    (net (code "101") (name "Net-(J12-Pad6)") (class "Default")
      (node (ref "J12") (pin "6") (pinfunction "6_6") (pintype "passive"))
      (node (ref "U1") (pin "B6") (pinfunction "B6_B6") (pintype "passive"))
    )
    (net (code "102") (name "Net-(LED1-PadC)") (class "Default")
      (node (ref "LED1") (pin "C") (pinfunction "C_C") (pintype "passive"))
      (node (ref "R25") (pin "2") (pinfunction "2_2") (pintype "passive"))
    )
    (net (code "103") (name "Net-(LED2-PadC)") (class "Default")
      (node (ref "LED2") (pin "C") (pinfunction "C_C") (pintype "passive"))
      (node (ref "R23") (pin "2") (pinfunction "2_2") (pintype "passive"))
    )
    (net (code "104") (name "Net-(U7-IOUT)") (class "Default")
      (node (ref "U7") (pin "2") (pinfunction "IOUT_2") (pintype "passive"))
      (node (ref "U8") (pin "1") (pinfunction "ANODE_1") (pintype "passive"))
    )
    (net (code "105") (name "Net-(U7-REXT)") (class "Default")
      (node (ref "R18") (pin "1") (pinfunction "1_1") (pintype "passive"))
      (node (ref "U7") (pin "4") (pinfunction "REXT_4") (pintype "passive"))
    )
    (net (code "106") (name "Net-(U7-VS)") (class "Default")
      (node (ref "D2") (pin "C") (pinfunction "C_C") (pintype "passive"))
      (node (ref "R18") (pin "2") (pinfunction "2_2") (pintype "passive"))
      (node (ref "U7") (pin "5") (pinfunction "VS_5") (pintype "passive"))
    )
    (net (code "107") (name "Net-(U9-EN{slash}UVLO)") (class "Default")
      (node (ref "R19") (pin "1") (pinfunction "1_1") (pintype "passive"))
      (node (ref "R21") (pin "1") (pinfunction "1_1") (pintype "passive"))
      (node (ref "U9") (pin "3") (pinfunction "EN/UVLO_3") (pintype "input"))
    )
    (net (code "108") (name "Net-(U9-LX)") (class "Default")
      (node (ref "L1") (pin "1") (pinfunction "1_1") (pintype "passive"))
      (node (ref "U9") (pin "10") (pinfunction "LX_10") (pintype "output"))
    )
    (net (code "109") (name "Net-(U9-SS)") (class "Default")
      (node (ref "C31") (pin "1") (pinfunction "1_1") (pintype "passive"))
      (node (ref "U9") (pin "6") (pinfunction "SS_6") (pintype "input"))
    )
    (net (code "110") (name "Net-(U9-VCC)") (class "Default")
      (node (ref "C30") (pin "1") (pinfunction "1_1") (pintype "passive"))
      (node (ref "U9") (pin "4") (pinfunction "VCC_4") (pintype "power_in"))
    )
    (net (code "111") (name "V+") (class "Default")
      (node (ref "C27") (pin "2") (pinfunction "2_2") (pintype "passive"))
      (node (ref "FB3") (pin "2") (pinfunction "2_2") (pintype "passive"))
      (node (ref "J12") (pin "4") (pinfunction "4_4") (pintype "passive"))
      (node (ref "R19") (pin "2") (pinfunction "2_2") (pintype "passive"))
      (node (ref "U1") (pin "B4") (pinfunction "B4_B4") (pintype "passive"))
      (node (ref "U9") (pin "2") (pinfunction "VIN_2") (pintype "power_in"))
    )
    (net (code "112") (name "VDDA") (class "Default")
      (node (ref "J13") (pin "64") (pinfunction "64_64") (pintype "passive"))
      (node (ref "U1") (pin "A64") (pinfunction "A64_A64") (pintype "passive"))
    )
    (net (code "113") (name "V_IN") (class "Default")
      (node (ref "D1") (pin "A") (pinfunction "A_A") (pintype "passive"))
      (node (ref "J14") (pin "1") (pinfunction "1_1") (pintype "passive"))
      (node (ref "TVS1") (pin "C") (pinfunction "C_C") (pintype "passive"))
    )
    (net (code "114") (name "V_REF") (class "Default")
      (node (ref "J13") (pin "66") (pinfunction "66_66") (pintype "passive"))
      (node (ref "U1") (pin "A66") (pinfunction "A66_A66") (pintype "passive"))
    )
    (net (code "115") (name "unconnected-(ST1-Pad1)") (class "Default")
      (node (ref "ST1") (pin "1") (pinfunction "1_1") (pintype "passive"))
    )
    (net (code "116") (name "unconnected-(ST2-Pad1)") (class "Default")
      (node (ref "ST2") (pin "1") (pinfunction "1_1") (pintype "passive"))
    )
    (net (code "117") (name "unconnected-(ST3-Pad1)") (class "Default")
      (node (ref "ST3") (pin "1") (pinfunction "1_1") (pintype "passive"))
    )
    (net (code "118") (name "unconnected-(ST4-Pad1)") (class "Default")
      (node (ref "ST4") (pin "1") (pinfunction "1_1") (pintype "passive"))
    )
    (net (code "119") (name "unconnected-(TVS3-PadA)") (class "Default")
      (node (ref "TVS3") (pin "A") (pinfunction "A_A") (pintype "passive"))
    )
    (net (code "120") (name "unconnected-(TVS3-PadC)") (class "Default")
      (node (ref "TVS3") (pin "C") (pinfunction "C_C") (pintype "passive"))
    )
    (net (code "121") (name "unconnected-(U7-NC-Pad1)") (class "Default")
      (node (ref "U7") (pin "1") (pinfunction "NC_1") (pintype "passive"))
    )
    (net (code "122") (name "unconnected-(U9-NC{slash}COMP-Pad7)") (class "Default")
      (node (ref "U9") (pin "7") (pinfunction "NC/COMP_7") (pintype "input+no_connect"))
    )
    (net (code "123") (name "unconnected-(U9-RESET-Pad8)") (class "Default")
      (node (ref "U9") (pin "8") (pinfunction "RESET_8") (pintype "open_collector"))
    )
  )
)
